# AD834_Mixer.net
KiCad netlist of a schematic drawn in Altium Designer
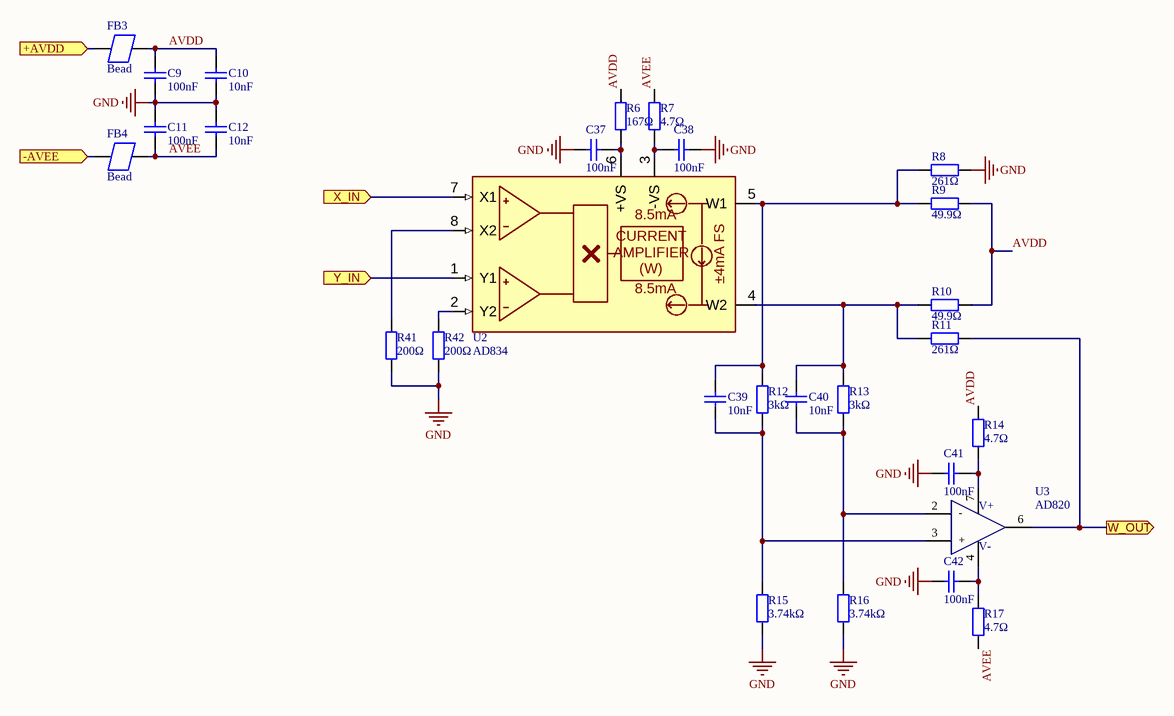
[diagram p0: AD834_Mixer.SchDoc]

(export (version "E")
  (design (tool "Eeschema 10.0.6"))
  (components
    (comp (ref "C9")
      (value "100nF")
      (footprint "0603_C")
      (description "贴片电容")
      (libsource (lib "Miscellaneous Devices LC") (part "0603 100nF (104) 10% 50V"))
    )
    (comp (ref "C10")
      (value "10nF")
      (footprint "0603_C")
      (description "贴片电容")
      (libsource (lib "Miscellaneous Devices LC") (part "0603 10nF (103) 10% 50V"))
    )
    (comp (ref "C11")
      (value "100nF")
      (footprint "0603_C")
      (description "贴片电容")
      (libsource (lib "Miscellaneous Devices LC") (part "0603 100nF (104) 10% 50V"))
    )
    (comp (ref "C12")
      (value "10nF")
      (footprint "0603_C")
      (description "贴片电容")
      (libsource (lib "Miscellaneous Devices LC") (part "0603 10nF (103) 10% 50V"))
    )
    (comp (ref "C37")
      (value "100nF")
      (footprint "0603_C")
      (description "贴片电容")
      (libsource (lib "Miscellaneous Devices LC") (part "0603 100nF (104) 10% 50V"))
    )
    (comp (ref "C38")
      (value "100nF")
      (footprint "0603_C")
      (description "贴片电容")
      (libsource (lib "Miscellaneous Devices LC") (part "0603 100nF (104) 10% 50V"))
    )
    (comp (ref "C39")
      (value "10nF")
      (footprint "0603_C")
      (description "贴片电容")
      (libsource (lib "Miscellaneous Devices LC") (part "0603 10nF (103) 10% 50V"))
    )
    (comp (ref "C40")
      (value "10nF")
      (footprint "0603_C")
      (description "贴片电容")
      (libsource (lib "Miscellaneous Devices LC") (part "0603 10nF (103) 10% 50V"))
    )
    (comp (ref "C41")
      (value "100nF")
      (footprint "0603_C")
      (description "贴片电容")
      (libsource (lib "Miscellaneous Devices LC") (part "0603 100nF (104) 10% 50V"))
    )
    (comp (ref "C42")
      (value "100nF")
      (footprint "0603_C")
      (description "贴片电容")
      (libsource (lib "Miscellaneous Devices LC") (part "0603 100nF (104) 10% 50V"))
    )
    (comp (ref "FB3") (value "Bead") (footprint "0805_L") (libsource (lib "OlvkLib") (part "Bead")))
    (comp (ref "FB4") (value "Bead") (footprint "0805_L") (libsource (lib "OlvkLib") (part "Bead")))
    (comp (ref "R6")
      (value "167Ω")
      (footprint "0603_R")
      (description "贴片电阻")
      (libsource (lib "") (part "0603 49.9Ω (49R9) 1%_1"))
    )
    (comp (ref "R7")
      (value "4.7Ω")
      (footprint "0603_R")
      (description "贴片电阻")
      (libsource (lib "") (part "0603 49.9Ω (49R9) 1%_1"))
    )
    (comp (ref "R8")
      (value "261Ω")
      (footprint "0603_R")
      (description "贴片电阻")
      (libsource (lib "Miscellaneous Devices LC") (part "0603 49.9Ω (49R9) 1%"))
    )
    (comp (ref "R9")
      (value "49.9Ω")
      (footprint "0603_R")
      (description "贴片电阻")
      (libsource (lib "Miscellaneous Devices LC") (part "0603 49.9Ω (49R9) 1%"))
    )
    (comp (ref "R10")
      (value "49.9Ω")
      (footprint "0603_R")
      (description "贴片电阻")
      (libsource (lib "Miscellaneous Devices LC") (part "0603 49.9Ω (49R9) 1%"))
    )
    (comp (ref "R11")
      (value "261Ω")
      (footprint "0603_R")
      (description "贴片电阻")
      (libsource (lib "Miscellaneous Devices LC") (part "0603 49.9Ω (49R9) 1%"))
    )
    (comp (ref "R12")
      (value "3kΩ")
      (footprint "0603_R")
      (description "贴片电阻")
      (libsource (lib "Miscellaneous Devices LC") (part "0603 3KΩ (3001) 1%"))
    )
    (comp (ref "R13")
      (value "3kΩ")
      (footprint "0603_R")
      (description "贴片电阻")
      (libsource (lib "Miscellaneous Devices LC") (part "0603 3KΩ (3001) 1%"))
    )
    (comp (ref "R14")
      (value "4.7Ω")
      (footprint "0603_R")
      (description "贴片电阻")
      (libsource (lib "") (part "0603 49.9Ω (49R9) 1%_1"))
    )
    (comp (ref "R15")
      (value "3.74kΩ")
      (footprint "0603_R")
      (description "贴片电阻")
      (libsource (lib "Miscellaneous Devices LC") (part "0603 3KΩ (3001) 1%"))
    )
    (comp (ref "R16")
      (value "3.74kΩ")
      (footprint "0603_R")
      (description "贴片电阻")
      (libsource (lib "Miscellaneous Devices LC") (part "0603 3KΩ (3001) 1%"))
    )
    (comp (ref "R17")
      (value "4.7Ω")
      (footprint "0603_R")
      (description "贴片电阻")
      (libsource (lib "") (part "0603 49.9Ω (49R9) 1%_1"))
    )
    (comp (ref "R41")
      (value "200Ω")
      (footprint "0603_R")
      (description "贴片电阻")
      (libsource (lib "Miscellaneous Devices LC") (part "0603 200Ω (2000) 1%"))
    )
    (comp (ref "R42")
      (value "200Ω")
      (footprint "0603_R")
      (description "贴片电阻")
      (libsource (lib "Miscellaneous Devices LC") (part "0603 200Ω (2000) 1%"))
    )
    (comp (ref "U2")
      (value "AD834")
      (footprint "SOIC127P600X175-8M")
      (libsource (lib "OlvkLib") (part "AD834"))
    )
    (comp (ref "U3")
      (value "AD820")
      (footprint "SOIC127P600X175-8M")
      (description "单路、14MHz、多路复用器友好型、低噪声、零漂移、RRO、CMOS 精密运算放大器")
      (libsource (lib "OlvkLib") (part "OPA189"))
    )
  )
  (nets
    (net (code "1") (name "/+AVDD") (class "Default")
      (node (ref "FB3") (pin "1") (pinfunction "1_1") (pintype "passive"))
    )
    (net (code "2") (name "/-AVEE") (class "Default")
      (node (ref "FB4") (pin "1") (pinfunction "1_1") (pintype "passive"))
    )
    (net (code "3") (name "/AVDD") (class "Default")
      (node (ref "C10") (pin "2") (pinfunction "2_2") (pintype "passive"))
      (node (ref "C9") (pin "2") (pinfunction "2_2") (pintype "passive"))
      (node (ref "FB3") (pin "2") (pinfunction "2_2") (pintype "passive"))
      (node (ref "R10") (pin "1") (pinfunction "1_1") (pintype "passive"))
      (node (ref "R14") (pin "1") (pinfunction "1_1") (pintype "passive"))
      (node (ref "R6") (pin "1") (pinfunction "1_1") (pintype "passive"))
      (node (ref "R9") (pin "1") (pinfunction "1_1") (pintype "passive"))
    )
    (net (code "4") (name "/AVEE") (class "Default")
      (node (ref "C11") (pin "2") (pinfunction "2_2") (pintype "passive"))
      (node (ref "C12") (pin "2") (pinfunction "2_2") (pintype "passive"))
      (node (ref "FB4") (pin "2") (pinfunction "2_2") (pintype "passive"))
      (node (ref "R17") (pin "2") (pinfunction "2_2") (pintype "passive"))
      (node (ref "R7") (pin "1") (pinfunction "1_1") (pintype "passive"))
    )
    (net (code "5") (name "/W_OUT") (class "Default")
      (node (ref "R11") (pin "1") (pinfunction "1_1") (pintype "passive"))
      (node (ref "U3") (pin "6") (pinfunction "1_6") (pintype "passive"))
    )
    (net (code "6") (name "/X_IN") (class "Default")
      (node (ref "U2") (pin "7") (pinfunction "X1_7") (pintype "input"))
    )
    (net (code "7") (name "/Y_IN") (class "Default")
      (node (ref "U2") (pin "1") (pinfunction "Y1_1") (pintype "input"))
    )
    (net (code "8") (name "GND") (class "Default")
      (node (ref "C10") (pin "1") (pinfunction "1_1") (pintype "passive"))
      (node (ref "C11") (pin "1") (pinfunction "1_1") (pintype "passive"))
      (node (ref "C12") (pin "1") (pinfunction "1_1") (pintype "passive"))
      (node (ref "C37") (pin "1") (pinfunction "1_1") (pintype "passive"))
      (node (ref "C38") (pin "1") (pinfunction "1_1") (pintype "passive"))
      (node (ref "C41") (pin "2") (pinfunction "2_2") (pintype "passive"))
      (node (ref "C42") (pin "2") (pinfunction "2_2") (pintype "passive"))
      (node (ref "C9") (pin "1") (pinfunction "1_1") (pintype "passive"))
      (node (ref "R15") (pin "1") (pinfunction "1_1") (pintype "passive"))
      (node (ref "R16") (pin "1") (pinfunction "1_1") (pintype "passive"))
      (node (ref "R41") (pin "1") (pinfunction "1_1") (pintype "passive"))
      (node (ref "R42") (pin "1") (pinfunction "1_1") (pintype "passive"))
      (node (ref "R8") (pin "1") (pinfunction "1_1") (pintype "passive"))
    )
    (net (code "9") (name "Net-(C39-Pad1)") (class "Default")
      (node (ref "C39") (pin "1") (pinfunction "1_1") (pintype "passive"))
      (node (ref "R12") (pin "1") (pinfunction "1_1") (pintype "passive"))
      (node (ref "R15") (pin "2") (pinfunction "2_2") (pintype "passive"))
      (node (ref "U3") (pin "3") (pinfunction "3_3") (pintype "passive"))
    )
    (net (code "10") (name "Net-(C40-Pad1)") (class "Default")
      (node (ref "C40") (pin "1") (pinfunction "1_1") (pintype "passive"))
      (node (ref "R13") (pin "1") (pinfunction "1_1") (pintype "passive"))
      (node (ref "R16") (pin "2") (pinfunction "2_2") (pintype "passive"))
      (node (ref "U3") (pin "2") (pinfunction "2_2") (pintype "passive"))
    )
    (net (code "11") (name "Net-(U2-+VS)") (class "Default")
      (node (ref "C37") (pin "2") (pinfunction "2_2") (pintype "passive"))
      (node (ref "R6") (pin "2") (pinfunction "2_2") (pintype "passive"))
      (node (ref "U2") (pin "6") (pinfunction "+VS_6") (pintype "power_in"))
    )
    (net (code "12") (name "Net-(U2--VS)") (class "Default")
      (node (ref "C38") (pin "2") (pinfunction "2_2") (pintype "passive"))
      (node (ref "R7") (pin "2") (pinfunction "2_2") (pintype "passive"))
      (node (ref "U2") (pin "3") (pinfunction "-VS_3") (pintype "power_in"))
    )
    (net (code "13") (name "Net-(U2-W1)") (class "Default")
      (node (ref "C39") (pin "2") (pinfunction "2_2") (pintype "passive"))
      (node (ref "R12") (pin "2") (pinfunction "2_2") (pintype "passive"))
      (node (ref "R8") (pin "2") (pinfunction "2_2") (pintype "passive"))
      (node (ref "R9") (pin "2") (pinfunction "2_2") (pintype "passive"))
      (node (ref "U2") (pin "5") (pinfunction "W1_5") (pintype "open_collector"))
    )
    (net (code "14") (name "Net-(U2-W2)") (class "Default")
      (node (ref "C40") (pin "2") (pinfunction "2_2") (pintype "passive"))
      (node (ref "R10") (pin "2") (pinfunction "2_2") (pintype "passive"))
      (node (ref "R11") (pin "2") (pinfunction "2_2") (pintype "passive"))
      (node (ref "R13") (pin "2") (pinfunction "2_2") (pintype "passive"))
      (node (ref "U2") (pin "4") (pinfunction "W2_4") (pintype "open_collector"))
    )
    (net (code "15") (name "Net-(U2-X2)") (class "Default")
      (node (ref "R41") (pin "2") (pinfunction "2_2") (pintype "passive"))
      (node (ref "U2") (pin "8") (pinfunction "X2_8") (pintype "input"))
    )
    (net (code "16") (name "Net-(U2-Y2)") (class "Default")
      (node (ref "R42") (pin "2") (pinfunction "2_2") (pintype "passive"))
      (node (ref "U2") (pin "2") (pinfunction "Y2_2") (pintype "input"))
    )
    (net (code "17") (name "Net-(U3-VCC+)") (class "Default")
      (node (ref "C41") (pin "1") (pinfunction "1_1") (pintype "passive"))
      (node (ref "R14") (pin "2") (pinfunction "2_2") (pintype "passive"))
      (node (ref "U3") (pin "7") (pinfunction "VCC+_7") (pintype "passive"))
    )
    (net (code "18") (name "Net-(U3-VCC-)") (class "Default")
      (node (ref "C42") (pin "1") (pinfunction "1_1") (pintype "passive"))
      (node (ref "R17") (pin "1") (pinfunction "1_1") (pintype "passive"))
      (node (ref "U3") (pin "4") (pinfunction "VCC-_4") (pintype "passive"))
    )
  )
)
